# 07_Analog_Buffer.net
KiCad netlist of a schematic drawn in Altium Designer
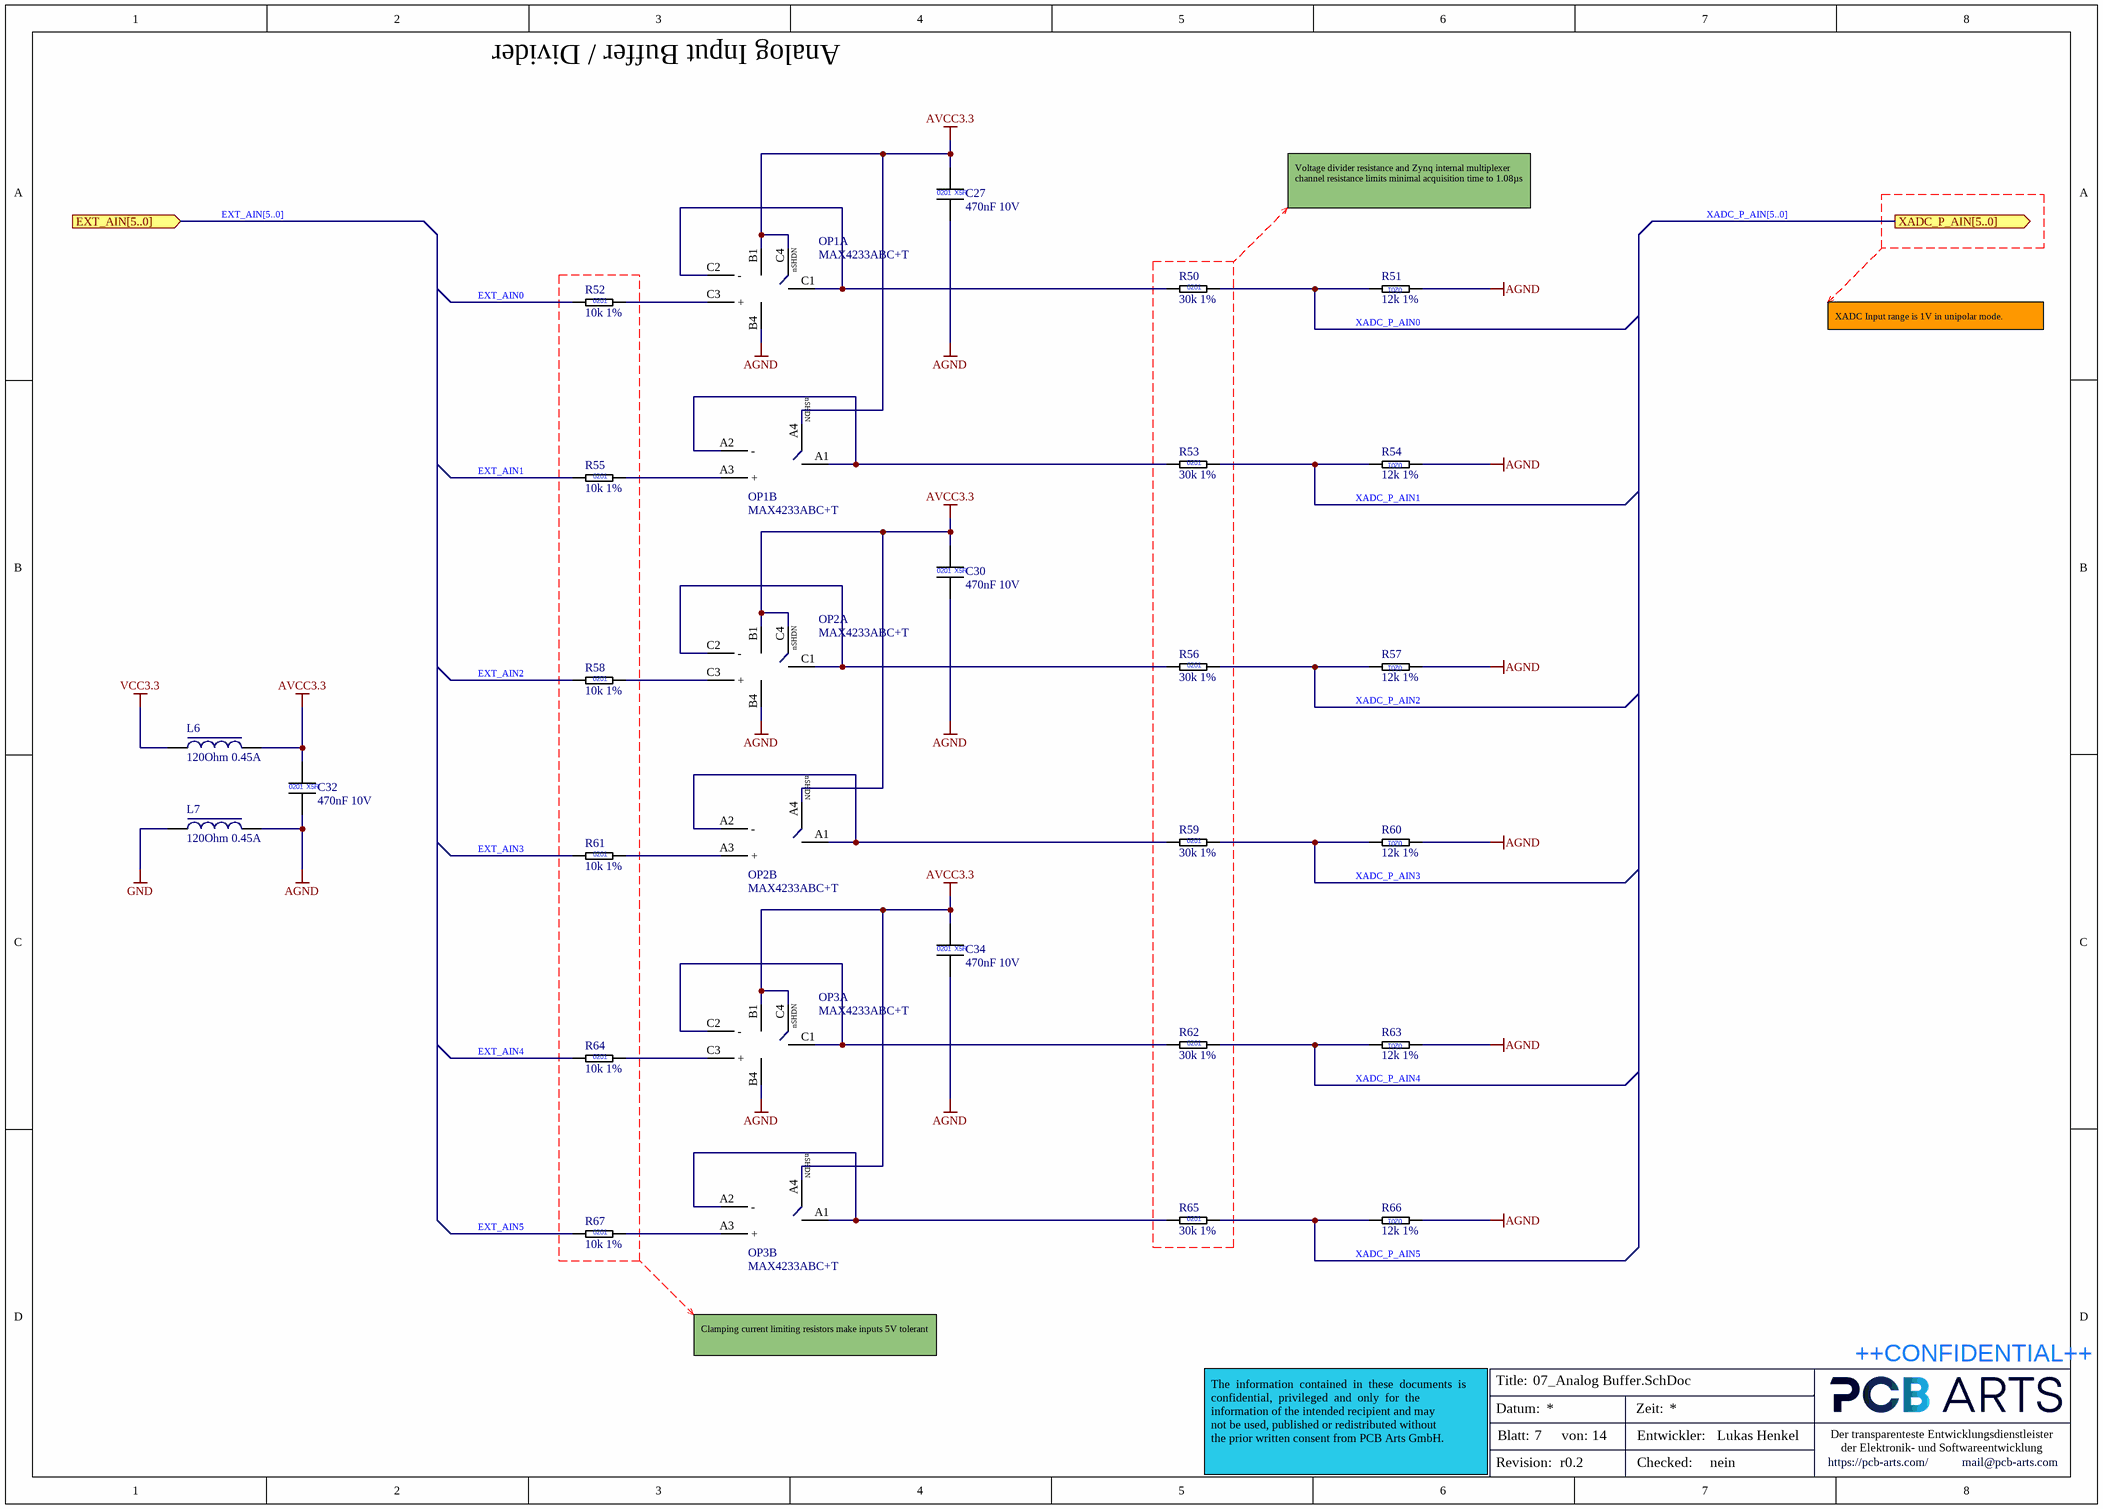
[diagram p0: 07_Analog Buffer.SchDoc]

(export (version "E")
  (design (tool "Eeschema 10.0.6"))
  (components
    (comp (ref "C27")
      (value "470nF 10V")
      (footprint "Zynq-Feather-HD:CAPC0603X03L")
      (description "Multilayer Ceramic Capacitors MLCC - SMD/SMT 0201 10VDC")
      (libsource (lib "Zynq-Feather-HD") (part "CAP_0201_470nF_10V"))
    )
    (comp (ref "C30")
      (value "470nF 10V")
      (footprint "Zynq-Feather-HD:CAPC0603X03L")
      (description "Multilayer Ceramic Capacitors MLCC - SMD/SMT 0201 10VDC")
      (libsource (lib "Zynq-Feather-HD") (part "CAP_0201_470nF_10V"))
    )
    (comp (ref "C32")
      (value "470nF 10V")
      (footprint "Zynq-Feather-HD:CAPC0603X03L")
      (description "Multilayer Ceramic Capacitors MLCC - SMD/SMT 0201 10VDC")
      (libsource (lib "Zynq-Feather-HD") (part "CAP_0201_470nF_10V"))
    )
    (comp (ref "C34")
      (value "470nF 10V")
      (footprint "Zynq-Feather-HD:CAPC0603X03L")
      (description "Multilayer Ceramic Capacitors MLCC - SMD/SMT 0201 10VDC")
      (libsource (lib "Zynq-Feather-HD") (part "CAP_0201_470nF_10V"))
    )
    (comp (ref "L6")
      (value "120Ohm 0.45A")
      (footprint "Zynq-Feather-HD:INDC0603X03L")
      (description "Ferrite Bead 0201 120Ohm 0.45A 25%")
      (fields (field (name "MANUFACTURER") "Taiyo Yuden"))
      (libsource (lib "Zynq-Feather-HD") (part "FLT_0201_120Ohm_0.45A"))
    )
    (comp (ref "L7")
      (value "120Ohm 0.45A")
      (footprint "Zynq-Feather-HD:INDC0603X03L")
      (description "Ferrite Bead 0201 120Ohm 0.45A 25%")
      (fields (field (name "MANUFACTURER") "Taiyo Yuden"))
      (libsource (lib "Zynq-Feather-HD") (part "FLT_0201_120Ohm_0.45A"))
    )
    (comp (ref "OP1")
      (value "MAX4233ABC+T")
      (footprint "Zynq-Feather-HD:BGA10C50P4X3_202X154X69")
      (description "High-Output-Drive, 10MHz, 10V/μs,Rail-to-Rail I/O Op Amps with Shutdown")
      (fields (field (name "MANUFACTURER") "Maxim Integrated"))
      (libsource (lib "Zynq-Feather-HD") (part "MAX4233ABC+T_High-Output-Drive, 10MHz, 10V/μs,Rail-to-Rail I/O Op Amp"))
    )
    (comp (ref "OP2")
      (value "MAX4233ABC+T")
      (footprint "Zynq-Feather-HD:BGA10C50P4X3_202X154X69")
      (description "High-Output-Drive, 10MHz, 10V/μs,Rail-to-Rail I/O Op Amps with Shutdown")
      (fields (field (name "MANUFACTURER") "Maxim Integrated"))
      (libsource (lib "Zynq-Feather-HD") (part "MAX4233ABC+T_High-Output-Drive, 10MHz, 10V/μs,Rail-to-Rail I/O Op Amp"))
    )
    (comp (ref "OP3")
      (value "MAX4233ABC+T")
      (footprint "Zynq-Feather-HD:BGA10C50P4X3_202X154X69")
      (description "High-Output-Drive, 10MHz, 10V/μs,Rail-to-Rail I/O Op Amps with Shutdown")
      (fields (field (name "MANUFACTURER") "Maxim Integrated"))
      (libsource (lib "Zynq-Feather-HD") (part "MAX4233ABC+T_High-Output-Drive, 10MHz, 10V/μs,Rail-to-Rail I/O Op Amp"))
    )
    (comp (ref "R50")
      (value "30k 1%")
      (footprint "Zynq-Feather-HD:RESC0603X03L")
      (description "Thick Film Resistors - SMD 30K OHM 1%")
      (libsource (lib "Zynq-Feather-HD") (part "RES_0201_30k_1%"))
    )
    (comp (ref "R51")
      (value "12k 1%")
      (footprint "Zynq-Feather-HD:RESC0603X03L")
      (description "Thick Film Resistors - SMD 12K OHM 1%")
      (libsource (lib "Zynq-Feather-HD") (part "RES_0201_12k_1%"))
    )
    (comp (ref "R52")
      (value "10k 1%")
      (footprint "Zynq-Feather-HD:RESC0603X03L")
      (description "Thick Film Resistors - SMD 10K OHM 1%")
      (libsource (lib "Zynq-Feather-HD") (part "RES_0201_10k_1%"))
    )
    (comp (ref "R53")
      (value "30k 1%")
      (footprint "Zynq-Feather-HD:RESC0603X03L")
      (description "Thick Film Resistors - SMD 30K OHM 1%")
      (libsource (lib "Zynq-Feather-HD") (part "RES_0201_30k_1%"))
    )
    (comp (ref "R54")
      (value "12k 1%")
      (footprint "Zynq-Feather-HD:RESC0603X03L")
      (description "Thick Film Resistors - SMD 12K OHM 1%")
      (libsource (lib "Zynq-Feather-HD") (part "RES_0201_12k_1%"))
    )
    (comp (ref "R55")
      (value "10k 1%")
      (footprint "Zynq-Feather-HD:RESC0603X03L")
      (description "Thick Film Resistors - SMD 10K OHM 1%")
      (libsource (lib "Zynq-Feather-HD") (part "RES_0201_10k_1%"))
    )
    (comp (ref "R56")
      (value "30k 1%")
      (footprint "Zynq-Feather-HD:RESC0603X03L")
      (description "Thick Film Resistors - SMD 30K OHM 1%")
      (libsource (lib "Zynq-Feather-HD") (part "RES_0201_30k_1%"))
    )
    (comp (ref "R57")
      (value "12k 1%")
      (footprint "Zynq-Feather-HD:RESC0603X03L")
      (description "Thick Film Resistors - SMD 12K OHM 1%")
      (libsource (lib "Zynq-Feather-HD") (part "RES_0201_12k_1%"))
    )
    (comp (ref "R58")
      (value "10k 1%")
      (footprint "Zynq-Feather-HD:RESC0603X03L")
      (description "Thick Film Resistors - SMD 10K OHM 1%")
      (libsource (lib "Zynq-Feather-HD") (part "RES_0201_10k_1%"))
    )
    (comp (ref "R59")
      (value "30k 1%")
      (footprint "Zynq-Feather-HD:RESC0603X03L")
      (description "Thick Film Resistors - SMD 30K OHM 1%")
      (libsource (lib "Zynq-Feather-HD") (part "RES_0201_30k_1%"))
    )
    (comp (ref "R60")
      (value "12k 1%")
      (footprint "Zynq-Feather-HD:RESC0603X03L")
      (description "Thick Film Resistors - SMD 12K OHM 1%")
      (libsource (lib "Zynq-Feather-HD") (part "RES_0201_12k_1%"))
    )
    (comp (ref "R61")
      (value "10k 1%")
      (footprint "Zynq-Feather-HD:RESC0603X03L")
      (description "Thick Film Resistors - SMD 10K OHM 1%")
      (libsource (lib "Zynq-Feather-HD") (part "RES_0201_10k_1%"))
    )
    (comp (ref "R62")
      (value "30k 1%")
      (footprint "Zynq-Feather-HD:RESC0603X03L")
      (description "Thick Film Resistors - SMD 30K OHM 1%")
      (libsource (lib "Zynq-Feather-HD") (part "RES_0201_30k_1%"))
    )
    (comp (ref "R63")
      (value "12k 1%")
      (footprint "Zynq-Feather-HD:RESC0603X03L")
      (description "Thick Film Resistors - SMD 12K OHM 1%")
      (libsource (lib "Zynq-Feather-HD") (part "RES_0201_12k_1%"))
    )
    (comp (ref "R64")
      (value "10k 1%")
      (footprint "Zynq-Feather-HD:RESC0603X03L")
      (description "Thick Film Resistors - SMD 10K OHM 1%")
      (libsource (lib "Zynq-Feather-HD") (part "RES_0201_10k_1%"))
    )
    (comp (ref "R65")
      (value "30k 1%")
      (footprint "Zynq-Feather-HD:RESC0603X03L")
      (description "Thick Film Resistors - SMD 30K OHM 1%")
      (libsource (lib "Zynq-Feather-HD") (part "RES_0201_30k_1%"))
    )
    (comp (ref "R66")
      (value "12k 1%")
      (footprint "Zynq-Feather-HD:RESC0603X03L")
      (description "Thick Film Resistors - SMD 12K OHM 1%")
      (libsource (lib "Zynq-Feather-HD") (part "RES_0201_12k_1%"))
    )
    (comp (ref "R67")
      (value "10k 1%")
      (footprint "Zynq-Feather-HD:RESC0603X03L")
      (description "Thick Film Resistors - SMD 10K OHM 1%")
      (libsource (lib "Zynq-Feather-HD") (part "RES_0201_10k_1%"))
    )
  )
  (nets
    (net (code "1") (name "/EXT_AIN0") (class "Default")
      (node (ref "R52") (pin "1") (pinfunction "1_1") (pintype "passive"))
    )
    (net (code "2") (name "/EXT_AIN1") (class "Default")
      (node (ref "R55") (pin "1") (pinfunction "1_1") (pintype "passive"))
    )
    (net (code "3") (name "/EXT_AIN2") (class "Default")
      (node (ref "R58") (pin "1") (pinfunction "1_1") (pintype "passive"))
    )
    (net (code "4") (name "/EXT_AIN3") (class "Default")
      (node (ref "R61") (pin "1") (pinfunction "1_1") (pintype "passive"))
    )
    (net (code "5") (name "/EXT_AIN4") (class "Default")
      (node (ref "R64") (pin "1") (pinfunction "1_1") (pintype "passive"))
    )
    (net (code "6") (name "/EXT_AIN5") (class "Default")
      (node (ref "R67") (pin "1") (pinfunction "1_1") (pintype "passive"))
    )
    (net (code "8") (name "/XADC_P_AIN0") (class "Default")
      (node (ref "R50") (pin "2") (pinfunction "2_2") (pintype "passive"))
      (node (ref "R51") (pin "2") (pinfunction "2_2") (pintype "passive"))
    )
    (net (code "9") (name "/XADC_P_AIN1") (class "Default")
      (node (ref "R53") (pin "2") (pinfunction "2_2") (pintype "passive"))
      (node (ref "R54") (pin "2") (pinfunction "2_2") (pintype "passive"))
    )
    (net (code "10") (name "/XADC_P_AIN2") (class "Default")
      (node (ref "R56") (pin "2") (pinfunction "2_2") (pintype "passive"))
      (node (ref "R57") (pin "2") (pinfunction "2_2") (pintype "passive"))
    )
    (net (code "11") (name "/XADC_P_AIN3") (class "Default")
      (node (ref "R59") (pin "2") (pinfunction "2_2") (pintype "passive"))
      (node (ref "R60") (pin "2") (pinfunction "2_2") (pintype "passive"))
    )
    (net (code "12") (name "/XADC_P_AIN4") (class "Default")
      (node (ref "R62") (pin "2") (pinfunction "2_2") (pintype "passive"))
      (node (ref "R63") (pin "2") (pinfunction "2_2") (pintype "passive"))
    )
    (net (code "13") (name "/XADC_P_AIN5") (class "Default")
      (node (ref "R65") (pin "2") (pinfunction "2_2") (pintype "passive"))
      (node (ref "R66") (pin "2") (pinfunction "2_2") (pintype "passive"))
    )
    (net (code "15") (name "AGND") (class "Default")
      (node (ref "C27") (pin "2") (pinfunction "2_2") (pintype "passive"))
      (node (ref "C30") (pin "2") (pinfunction "2_2") (pintype "passive"))
      (node (ref "C32") (pin "2") (pinfunction "2_2") (pintype "passive"))
      (node (ref "C34") (pin "2") (pinfunction "2_2") (pintype "passive"))
      (node (ref "L7") (pin "2") (pinfunction "2_2") (pintype "passive"))
      (node (ref "OP1") (pin "B4") (pinfunction "V-_B4") (pintype "passive"))
      (node (ref "OP2") (pin "B4") (pinfunction "V-_B4") (pintype "passive"))
      (node (ref "OP3") (pin "B4") (pinfunction "V-_B4") (pintype "passive"))
      (node (ref "R51") (pin "1") (pinfunction "1_1") (pintype "passive"))
      (node (ref "R54") (pin "1") (pinfunction "1_1") (pintype "passive"))
      (node (ref "R57") (pin "1") (pinfunction "1_1") (pintype "passive"))
      (node (ref "R60") (pin "1") (pinfunction "1_1") (pintype "passive"))
      (node (ref "R63") (pin "1") (pinfunction "1_1") (pintype "passive"))
      (node (ref "R66") (pin "1") (pinfunction "1_1") (pintype "passive"))
    )
    (net (code "16") (name "AVCC3.3") (class "Default")
      (node (ref "C27") (pin "1") (pinfunction "1_1") (pintype "passive"))
      (node (ref "C30") (pin "1") (pinfunction "1_1") (pintype "passive"))
      (node (ref "C32") (pin "1") (pinfunction "1_1") (pintype "passive"))
      (node (ref "C34") (pin "1") (pinfunction "1_1") (pintype "passive"))
      (node (ref "L6") (pin "2") (pinfunction "2_2") (pintype "passive"))
      (node (ref "OP1") (pin "A4") (pinfunction "~{SHDN}_A4") (pintype "passive"))
      (node (ref "OP1") (pin "B1") (pinfunction "V+_B1") (pintype "passive"))
      (node (ref "OP1") (pin "C4") (pinfunction "~{SHDN}_C4") (pintype "passive"))
      (node (ref "OP2") (pin "A4") (pinfunction "~{SHDN}_A4") (pintype "passive"))
      (node (ref "OP2") (pin "B1") (pinfunction "V+_B1") (pintype "passive"))
      (node (ref "OP2") (pin "C4") (pinfunction "~{SHDN}_C4") (pintype "passive"))
      (node (ref "OP3") (pin "A4") (pinfunction "~{SHDN}_A4") (pintype "passive"))
      (node (ref "OP3") (pin "B1") (pinfunction "V+_B1") (pintype "passive"))
      (node (ref "OP3") (pin "C4") (pinfunction "~{SHDN}_C4") (pintype "passive"))
    )
    (net (code "17") (name "GND") (class "Default")
      (node (ref "L7") (pin "1") (pinfunction "1_1") (pintype "passive"))
    )
    (net (code "18") (name "Net-(OP1A-+)") (class "Default")
      (node (ref "OP1") (pin "C3") (pinfunction "+_C3") (pintype "passive"))
      (node (ref "R52") (pin "2") (pinfunction "2_2") (pintype "passive"))
    )
    (net (code "19") (name "Net-(OP1A--)") (class "Default")
      (node (ref "OP1") (pin "C1") (pinfunction "OUT_C1") (pintype "passive"))
      (node (ref "OP1") (pin "C2") (pinfunction "-_C2") (pintype "passive"))
      (node (ref "R50") (pin "1") (pinfunction "1_1") (pintype "passive"))
    )
    (net (code "20") (name "Net-(OP1B-+)") (class "Default")
      (node (ref "OP1") (pin "A3") (pinfunction "+_A3") (pintype "passive"))
      (node (ref "R55") (pin "2") (pinfunction "2_2") (pintype "passive"))
    )
    (net (code "21") (name "Net-(OP1B--)") (class "Default")
      (node (ref "OP1") (pin "A1") (pinfunction "OUT_B_A1") (pintype "passive"))
      (node (ref "OP1") (pin "A2") (pinfunction "-_A2") (pintype "passive"))
      (node (ref "R53") (pin "1") (pinfunction "1_1") (pintype "passive"))
    )
    (net (code "22") (name "Net-(OP2A-+)") (class "Default")
      (node (ref "OP2") (pin "C3") (pinfunction "+_C3") (pintype "passive"))
      (node (ref "R58") (pin "2") (pinfunction "2_2") (pintype "passive"))
    )
    (net (code "23") (name "Net-(OP2A--)") (class "Default")
      (node (ref "OP2") (pin "C1") (pinfunction "OUT_C1") (pintype "passive"))
      (node (ref "OP2") (pin "C2") (pinfunction "-_C2") (pintype "passive"))
      (node (ref "R56") (pin "1") (pinfunction "1_1") (pintype "passive"))
    )
    (net (code "24") (name "Net-(OP2B-+)") (class "Default")
      (node (ref "OP2") (pin "A3") (pinfunction "+_A3") (pintype "passive"))
      (node (ref "R61") (pin "2") (pinfunction "2_2") (pintype "passive"))
    )
    (net (code "25") (name "Net-(OP2B--)") (class "Default")
      (node (ref "OP2") (pin "A1") (pinfunction "OUT_B_A1") (pintype "passive"))
      (node (ref "OP2") (pin "A2") (pinfunction "-_A2") (pintype "passive"))
      (node (ref "R59") (pin "1") (pinfunction "1_1") (pintype "passive"))
    )
    (net (code "26") (name "Net-(OP3A-+)") (class "Default")
      (node (ref "OP3") (pin "C3") (pinfunction "+_C3") (pintype "passive"))
      (node (ref "R64") (pin "2") (pinfunction "2_2") (pintype "passive"))
    )
    (net (code "27") (name "Net-(OP3A--)") (class "Default")
      (node (ref "OP3") (pin "C1") (pinfunction "OUT_C1") (pintype "passive"))
      (node (ref "OP3") (pin "C2") (pinfunction "-_C2") (pintype "passive"))
      (node (ref "R62") (pin "1") (pinfunction "1_1") (pintype "passive"))
    )
    (net (code "28") (name "Net-(OP3B-+)") (class "Default")
      (node (ref "OP3") (pin "A3") (pinfunction "+_A3") (pintype "passive"))
      (node (ref "R67") (pin "2") (pinfunction "2_2") (pintype "passive"))
    )
    (net (code "29") (name "Net-(OP3B--)") (class "Default")
      (node (ref "OP3") (pin "A1") (pinfunction "OUT_B_A1") (pintype "passive"))
      (node (ref "OP3") (pin "A2") (pinfunction "-_A2") (pintype "passive"))
      (node (ref "R65") (pin "1") (pinfunction "1_1") (pintype "passive"))
    )
    (net (code "30") (name "VCC3.3") (class "Default")
      (node (ref "L6") (pin "1") (pinfunction "1_1") (pintype "passive"))
    )
  )
)
